# Sens_BME280.net
KiCad netlist of a schematic drawn in EAGLE
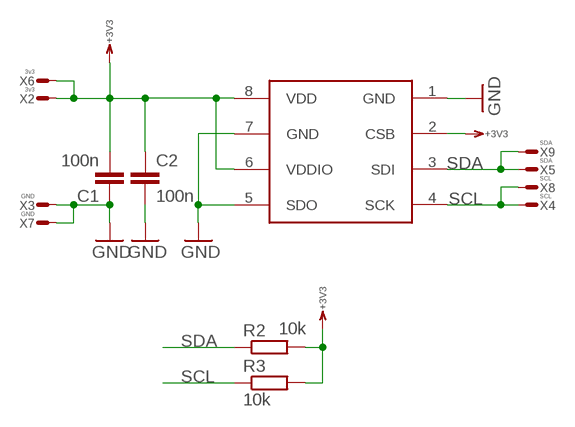
[diagram p0: schematic, sheet 1]

(export (version "E")
  (design (tool "Eeschema 10.0.6"))
  (components
    (comp (ref "C1")
      (value "100n")
      (footprint "eagle-import:0603")
      (libsource (lib "eagle-import") (part "C0603"))
    )
    (comp (ref "C2")
      (value "100n")
      (footprint "eagle-import:0603")
      (libsource (lib "eagle-import") (part "C0603"))
    )
    (comp (ref "IC1")
      (value "BME280")
      (footprint "eagle-import:BME280")
      (libsource (lib "eagle-import") (part "BME280"))
    )
    (comp (ref "R2")
      (value "10k")
      (footprint "eagle-import:0603")
      (libsource (lib "eagle-import") (part "R0603"))
    )
    (comp (ref "R3")
      (value "10k")
      (footprint "eagle-import:0603")
      (libsource (lib "eagle-import") (part "R0603"))
    )
    (comp (ref "X2")
      (value "3v3")
      (footprint "eagle-import:T1.6_0.9")
      (libsource (lib "eagle-import") (part "WIREPADT1.6/0.9"))
    )
    (comp (ref "X3")
      (value "GND")
      (footprint "eagle-import:T1.6_0.9")
      (libsource (lib "eagle-import") (part "WIREPADT1.6/0.9"))
    )
    (comp (ref "X4")
      (value "SCL")
      (footprint "eagle-import:T1.6_0.9")
      (libsource (lib "eagle-import") (part "WIREPADT1.6/0.9"))
    )
    (comp (ref "X5")
      (value "SDA")
      (footprint "eagle-import:T1.6_0.9")
      (libsource (lib "eagle-import") (part "WIREPADT1.6/0.9"))
    )
    (comp (ref "X6")
      (value "3v3")
      (footprint "eagle-import:T1.6_0.9")
      (libsource (lib "eagle-import") (part "WIREPADT1.6/0.9"))
    )
    (comp (ref "X7")
      (value "GND")
      (footprint "eagle-import:T1.6_0.9")
      (libsource (lib "eagle-import") (part "WIREPADT1.6/0.9"))
    )
    (comp (ref "X8")
      (value "SCL")
      (footprint "eagle-import:T1.6_0.9")
      (libsource (lib "eagle-import") (part "WIREPADT1.6/0.9"))
    )
    (comp (ref "X9")
      (value "SDA")
      (footprint "eagle-import:T1.6_0.9")
      (libsource (lib "eagle-import") (part "WIREPADT1.6/0.9"))
    )
  )
  (nets
    (net (code "1") (name "+3V3") (class "Default")
      (node (ref "C1") (pin "2") (pinfunction "2_2") (pintype "passive"))
      (node (ref "C2") (pin "1") (pinfunction "1_1") (pintype "passive"))
      (node (ref "IC1") (pin "2") (pinfunction "CSB_2") (pintype "bidirectional"))
      (node (ref "IC1") (pin "6") (pinfunction "VDDIO_6") (pintype "bidirectional"))
      (node (ref "IC1") (pin "8") (pinfunction "VDD_8") (pintype "bidirectional"))
      (node (ref "R2") (pin "2") (pinfunction "2_2") (pintype "passive"))
      (node (ref "R3") (pin "2") (pinfunction "2_2") (pintype "passive"))
      (node (ref "X2") (pin "1") (pinfunction "S_1") (pintype "passive"))
      (node (ref "X6") (pin "1") (pinfunction "S_1") (pintype "passive"))
    )
    (net (code "2") (name "/SCL") (class "Default")
      (node (ref "IC1") (pin "4") (pinfunction "SCK_4") (pintype "bidirectional"))
      (node (ref "R3") (pin "1") (pinfunction "1_1") (pintype "passive"))
      (node (ref "X4") (pin "1") (pinfunction "S_1") (pintype "passive"))
      (node (ref "X8") (pin "1") (pinfunction "S_1") (pintype "passive"))
    )
    (net (code "3") (name "/SDA") (class "Default")
      (node (ref "IC1") (pin "3") (pinfunction "SDI_3") (pintype "bidirectional"))
      (node (ref "R2") (pin "1") (pinfunction "1_1") (pintype "passive"))
      (node (ref "X5") (pin "1") (pinfunction "S_1") (pintype "passive"))
      (node (ref "X9") (pin "1") (pinfunction "S_1") (pintype "passive"))
    )
    (net (code "4") (name "GND") (class "Default")
      (node (ref "C1") (pin "1") (pinfunction "1_1") (pintype "passive"))
      (node (ref "C2") (pin "2") (pinfunction "2_2") (pintype "passive"))
      (node (ref "IC1") (pin "1") (pinfunction "GND_1") (pintype "bidirectional"))
      (node (ref "IC1") (pin "5") (pinfunction "SDO_5") (pintype "bidirectional"))
      (node (ref "IC1") (pin "7") (pinfunction "GND_7") (pintype "bidirectional"))
      (node (ref "X3") (pin "1") (pinfunction "S_1") (pintype "passive"))
      (node (ref "X7") (pin "1") (pinfunction "S_1") (pintype "passive"))
    )
  )
)
